# Power.net
KiCad netlist of a schematic drawn in Altium Designer
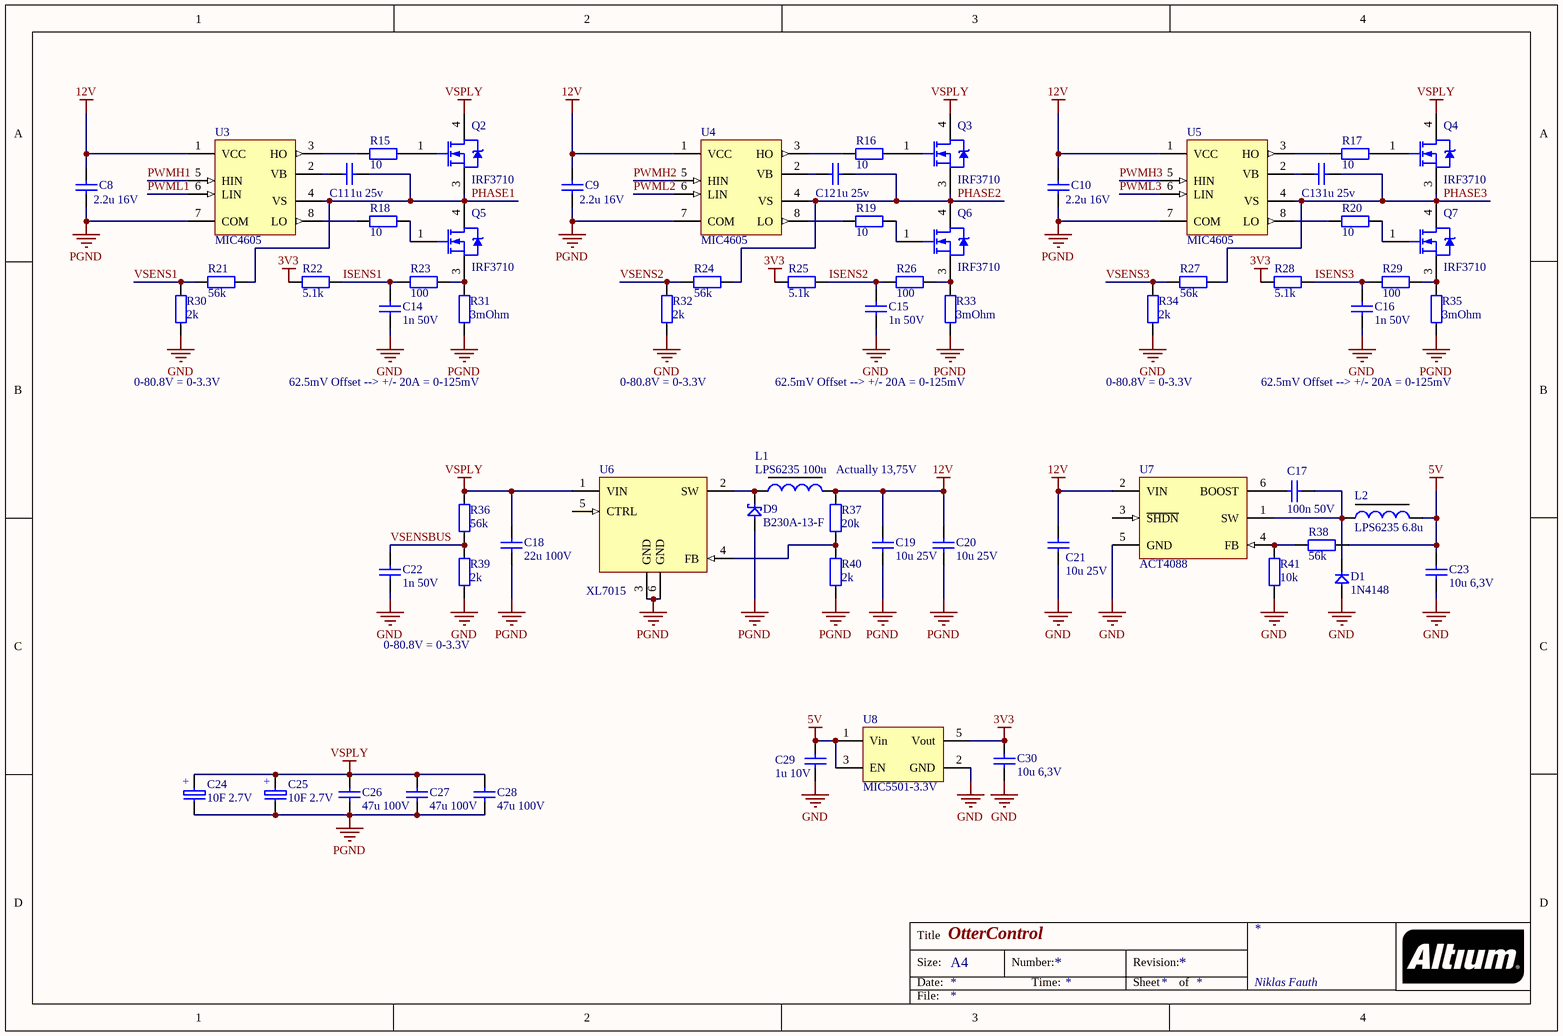
[diagram p0: Power.SchDoc]

(export (version "E")
  (design (tool "Eeschema 10.0.6"))
  (components
    (comp (ref "C8")
      (value "2.2u 16V")
      (footprint "C-0603-M")
      (description "Capacitor 2.2uF 16V")
      (libsource (lib "Passives") (part "C-0603-2u2-16V"))
    )
    (comp (ref "C9")
      (value "2.2u 16V")
      (footprint "C-0603-M")
      (description "Capacitor 2.2uF 16V")
      (libsource (lib "Passives") (part "C-0603-2u2-16V"))
    )
    (comp (ref "C10")
      (value "2.2u 16V")
      (footprint "C-0603-M")
      (description "Capacitor 2.2uF 16V")
      (libsource (lib "Passives") (part "C-0603-2u2-16V"))
    )
    (comp (ref "C11")
      (value "1u 25v")
      (footprint "C-0603-H")
      (description "Capacitor 1uF 25V")
      (libsource (lib "Passives") (part "C-0603-1u-25V"))
    )
    (comp (ref "C12")
      (value "1u 25v")
      (footprint "C-0603-H")
      (description "Capacitor 1uF 25V")
      (libsource (lib "Passives") (part "C-0603-1u-25V"))
    )
    (comp (ref "C13")
      (value "1u 25v")
      (footprint "C-0603-H")
      (description "Capacitor 1uF 25V")
      (libsource (lib "Passives") (part "C-0603-1u-25V"))
    )
    (comp (ref "C14")
      (value "1n 50V")
      (footprint "C-0603-H")
      (description "Capacitor 1nF 50V")
      (libsource (lib "Passives") (part "C-0603-1n-50V"))
    )
    (comp (ref "C15")
      (value "1n 50V")
      (footprint "C-0603-H")
      (description "Capacitor 1nF 50V")
      (libsource (lib "Passives") (part "C-0603-1n-50V"))
    )
    (comp (ref "C16")
      (value "1n 50V")
      (footprint "C-0603-H")
      (description "Capacitor 1nF 50V")
      (libsource (lib "Passives") (part "C-0603-1n-50V"))
    )
    (comp (ref "C17")
      (value "100n 50V")
      (footprint "C-0603-H")
      (description "Capacitor 100n 50V")
      (libsource (lib "Passives") (part "C-0603-100n-50V"))
    )
    (comp (ref "C18")
      (value "22u 100V")
      (footprint "C-2220")
      (description "Capacitor 47uF 100V")
      (libsource (lib "Passives") (part "C-2220-15u-100V"))
    )
    (comp (ref "C19")
      (value "10u 25V")
      (footprint "C-1206-H")
      (description "Capacitor 10uF 25V")
      (libsource (lib "Passives") (part "C-1206-10u-25V"))
    )
    (comp (ref "C20")
      (value "10u 25V")
      (footprint "C-1206-H")
      (description "Capacitor 10uF 25V")
      (libsource (lib "Passives") (part "C-1206-10u-25V"))
    )
    (comp (ref "C21")
      (value "10u 25V")
      (footprint "C-1206-H")
      (description "Capacitor 10uF 25V")
      (libsource (lib "Passives") (part "C-1206-10u-25V"))
    )
    (comp (ref "C22")
      (value "1n 50V")
      (footprint "C-0603-H")
      (description "Capacitor 1nF 50V")
      (libsource (lib "Passives") (part "C-0603-1n-50V"))
    )
    (comp (ref "C23")
      (value "10u 6,3V")
      (footprint "C-0603-H")
      (description "Capacitor 10uF 6,3V")
      (libsource (lib "Passives") (part "C-0603-10u-6,3V"))
    )
    (comp (ref "C24")
      (value "10F 2.7V")
      (footprint "12.5x31.5-angle")
      (description "supercap 10F 2.7V")
      (libsource (lib "Passives") (part "SC-10F-2.7V"))
    )
    (comp (ref "C25")
      (value "10F 2.7V")
      (footprint "12.5x31.5-angle")
      (description "supercap 10F 2.7V")
      (libsource (lib "Passives") (part "SC-10F-2.7V"))
    )
    (comp (ref "C26")
      (value "47u 100V")
      (footprint "C-2220")
      (description "Capacitor 47uF 100V")
      (libsource (lib "Passives") (part "C-2220-15u-100V"))
    )
    (comp (ref "C27")
      (value "47u 100V")
      (footprint "C-2220")
      (description "Capacitor 47uF 100V")
      (libsource (lib "Passives") (part "C-2220-15u-100V"))
    )
    (comp (ref "C28")
      (value "47u 100V")
      (footprint "C-2220")
      (description "Capacitor 47uF 100V")
      (libsource (lib "Passives") (part "C-2220-15u-100V"))
    )
    (comp (ref "C29")
      (value "1u 10V")
      (footprint "C-0603-M")
      (description "Capacitor 1uF 10V")
      (libsource (lib "Passives") (part "C-0603-1u-10V"))
    )
    (comp (ref "C30")
      (value "10u 6,3V")
      (footprint "C-0603-H")
      (description "Capacitor 10uF 6,3V")
      (libsource (lib "Passives") (part "C-0603-10u-6,3V"))
    )
    (comp (ref "D1")
      (value "1N4148")
      (footprint "SOD323F")
      (description "Diode 1N4148")
      (libsource (lib "advanced") (part "1N4148"))
    )
    (comp (ref "D9")
      (value "B230A-13-F")
      (footprint "DIODE-SMA")
      (libsource (lib "advanced") (part "D-B230A-13-F"))
    )
    (comp (ref "L1")
      (value "LPS6235 100u")
      (footprint "LPS6235")
      (libsource (lib "Passives") (part "L-LPS6235-68u"))
    )
    (comp (ref "L2")
      (value "LPS6235 6.8u")
      (footprint "LPS6235")
      (libsource (lib "Passives") (part "L-LPS6235-6u8"))
    )
    (comp (ref "Q2")
      (value "IRF3710")
      (footprint "ONSC-D2PAK-3-418B-04_V")
      (description "Power MOSFET, 37 A, 150 V, N-Channel Enhancement-Mode, 3-Pin D2PAK, Pb-Free, Tube")
      (fields (field (name "MANUFACTURER") "On Semiconductor") (field (name "PARTNUMBER") "NTB35N15G"))
      (libsource (lib "Altium Content Vault") (part "ONSC-NMOS-G1S3D4-3_C"))
    )
    (comp (ref "Q3")
      (value "IRF3710")
      (footprint "ONSC-D2PAK-3-418B-04_V")
      (description "Power MOSFET, 37 A, 150 V, N-Channel Enhancement-Mode, 3-Pin D2PAK, Pb-Free, Tube")
      (fields (field (name "MANUFACTURER") "On Semiconductor") (field (name "PARTNUMBER") "NTB35N15G"))
      (libsource (lib "Altium Content Vault") (part "ONSC-NMOS-G1S3D4-3_C"))
    )
    (comp (ref "Q4")
      (value "IRF3710")
      (footprint "ONSC-D2PAK-3-418B-04_V")
      (description "Power MOSFET, 37 A, 150 V, N-Channel Enhancement-Mode, 3-Pin D2PAK, Pb-Free, Tube")
      (fields (field (name "MANUFACTURER") "On Semiconductor") (field (name "PARTNUMBER") "NTB35N15G"))
      (libsource (lib "Altium Content Vault") (part "ONSC-NMOS-G1S3D4-3_C"))
    )
    (comp (ref "Q5")
      (value "IRF3710")
      (footprint "ONSC-D2PAK-3-418B-04_V")
      (description "Power MOSFET, 37 A, 150 V, N-Channel Enhancement-Mode, 3-Pin D2PAK, Pb-Free, Tube")
      (fields (field (name "MANUFACTURER") "On Semiconductor") (field (name "PARTNUMBER") "NTB35N15G"))
      (libsource (lib "Altium Content Vault") (part "ONSC-NMOS-G1S3D4-3_C"))
    )
    (comp (ref "Q6")
      (value "IRF3710")
      (footprint "ONSC-D2PAK-3-418B-04_V")
      (description "Power MOSFET, 37 A, 150 V, N-Channel Enhancement-Mode, 3-Pin D2PAK, Pb-Free, Tube")
      (fields (field (name "MANUFACTURER") "On Semiconductor") (field (name "PARTNUMBER") "NTB35N15G"))
      (libsource (lib "Altium Content Vault") (part "ONSC-NMOS-G1S3D4-3_C"))
    )
    (comp (ref "Q7")
      (value "IRF3710")
      (footprint "ONSC-D2PAK-3-418B-04_V")
      (description "Power MOSFET, 37 A, 150 V, N-Channel Enhancement-Mode, 3-Pin D2PAK, Pb-Free, Tube")
      (fields (field (name "MANUFACTURER") "On Semiconductor") (field (name "PARTNUMBER") "NTB35N15G"))
      (libsource (lib "Altium Content Vault") (part "ONSC-NMOS-G1S3D4-3_C"))
    )
    (comp (ref "R15")
      (value "10")
      (footprint "R-0603-H")
      (description "Resistor 10")
      (libsource (lib "Passives") (part "R-0603-10"))
    )
    (comp (ref "R16")
      (value "10")
      (footprint "R-0603-H")
      (description "Resistor 10")
      (libsource (lib "Passives") (part "R-0603-10"))
    )
    (comp (ref "R17")
      (value "10")
      (footprint "R-0603-H")
      (description "Resistor 10")
      (libsource (lib "Passives") (part "R-0603-10"))
    )
    (comp (ref "R18")
      (value "10")
      (footprint "R-0603-H")
      (description "Resistor 10")
      (libsource (lib "Passives") (part "R-0603-10"))
    )
    (comp (ref "R19")
      (value "10")
      (footprint "R-0603-H")
      (description "Resistor 10")
      (libsource (lib "Passives") (part "R-0603-10"))
    )
    (comp (ref "R20")
      (value "10")
      (footprint "R-0603-H")
      (description "Resistor 10")
      (libsource (lib "Passives") (part "R-0603-10"))
    )
    (comp (ref "R21")
      (value "56k")
      (footprint "R-0603-H")
      (description "Resistor 4k7")
      (libsource (lib "Passives") (part "R-0603-47k"))
    )
    (comp (ref "R22")
      (value "5.1k")
      (footprint "R-0603-H")
      (description "Resistor 5.1k")
      (libsource (lib "Passives") (part "R-0603-5k1"))
    )
    (comp (ref "R23")
      (value "100")
      (footprint "R-0603-H")
      (description "Resistor 100")
      (libsource (lib "Passives") (part "R-0603-100"))
    )
    (comp (ref "R24")
      (value "56k")
      (footprint "R-0603-H")
      (description "Resistor 4k7")
      (libsource (lib "Passives") (part "R-0603-47k"))
    )
    (comp (ref "R25")
      (value "5.1k")
      (footprint "R-0603-H")
      (description "Resistor 5.1k")
      (libsource (lib "Passives") (part "R-0603-5k1"))
    )
    (comp (ref "R26")
      (value "100")
      (footprint "R-0603-H")
      (description "Resistor 100")
      (libsource (lib "Passives") (part "R-0603-100"))
    )
    (comp (ref "R27")
      (value "56k")
      (footprint "R-0603-H")
      (description "Resistor 4k7")
      (libsource (lib "Passives") (part "R-0603-47k"))
    )
    (comp (ref "R28")
      (value "5.1k")
      (footprint "R-0603-H")
      (description "Resistor 5.1k")
      (libsource (lib "Passives") (part "R-0603-5k1"))
    )
    (comp (ref "R29")
      (value "100")
      (footprint "R-0603-H")
      (description "Resistor 100")
      (libsource (lib "Passives") (part "R-0603-100"))
    )
    (comp (ref "R30")
      (value "2k")
      (footprint "R-0603-M")
      (description "Resistor 2k")
      (libsource (lib "Passives") (part "R-0603-2k"))
    )
    (comp (ref "R31")
      (value "3mOhm")
      (footprint "R-1206-M")
      (description "Resistor 0")
      (libsource (lib "Passives") (part "R-1206-0"))
    )
    (comp (ref "R32")
      (value "2k")
      (footprint "R-0603-M")
      (description "Resistor 2k")
      (libsource (lib "Passives") (part "R-0603-2k"))
    )
    (comp (ref "R33")
      (value "3mOhm")
      (footprint "R-1206-M")
      (description "Resistor 0")
      (libsource (lib "Passives") (part "R-1206-0"))
    )
    (comp (ref "R34")
      (value "2k")
      (footprint "R-0603-M")
      (description "Resistor 2k")
      (libsource (lib "Passives") (part "R-0603-2k"))
    )
    (comp (ref "R35")
      (value "3mOhm")
      (footprint "R-1206-M")
      (description "Resistor 0")
      (libsource (lib "Passives") (part "R-1206-0"))
    )
    (comp (ref "R36")
      (value "56k")
      (footprint "R-0603-H")
      (description "Resistor 4k7")
      (libsource (lib "") (part "R-0603-47k_1"))
    )
    (comp (ref "R37")
      (value "20k")
      (footprint "R-0603-H")
      (description "Resistor 20k")
      (libsource (lib "Passives") (part "R-0603-20k"))
    )
    (comp (ref "R38")
      (value "56k")
      (footprint "R-0603-H")
      (description "Resistor 4k7")
      (libsource (lib "Passives") (part "R-0603-47k"))
    )
    (comp (ref "R39")
      (value "2k")
      (footprint "R-0603-M")
      (description "Resistor 2k")
      (libsource (lib "Passives") (part "R-0603-2k"))
    )
    (comp (ref "R40")
      (value "2k")
      (footprint "R-0603-H")
      (description "Resistor 2k")
      (libsource (lib "Passives") (part "R-0603-2k"))
    )
    (comp (ref "R41")
      (value "10k")
      (footprint "R-0603-H")
      (description "Resistor 15k")
      (libsource (lib "Passives") (part "R-0603-15k"))
    )
    (comp (ref "U3") (value "MIC4605") (footprint "SOIC-8") (libsource (lib "advanced") (part "MIC4605")))
    (comp (ref "U4") (value "MIC4605") (footprint "SOIC-8") (libsource (lib "advanced") (part "MIC4605")))
    (comp (ref "U5") (value "MIC4605") (footprint "SOIC-8") (libsource (lib "advanced") (part "MIC4605")))
    (comp (ref "U6")
      (value "XL7015")
      (footprint "DPAK127P970X238-6L")
      (description "High Voltage StepDown")
      (libsource (lib "advanced") (part "XL7015"))
    )
    (comp (ref "U7") (value "ACT4088") (footprint "SOT23-6") (libsource (lib "advanced") (part "ACT4088")))
    (comp (ref "U8")
      (value "MIC5501-3.3V")
      (footprint "SOT23-5")
      (libsource (lib "advanced") (part "MIC5501-3.3V"))
    )
  )
  (nets
    (net (code "1") (name "/ISENS1") (class "Default")
      (node (ref "C14") (pin "2") (pinfunction "2_2") (pintype "passive"))
      (node (ref "R22") (pin "2") (pinfunction "2_2") (pintype "passive"))
      (node (ref "R23") (pin "1") (pinfunction "1_1") (pintype "passive"))
    )
    (net (code "2") (name "/ISENS2") (class "Default")
      (node (ref "C15") (pin "2") (pinfunction "2_2") (pintype "passive"))
      (node (ref "R25") (pin "2") (pinfunction "2_2") (pintype "passive"))
      (node (ref "R26") (pin "1") (pinfunction "1_1") (pintype "passive"))
    )
    (net (code "3") (name "/ISENS3") (class "Default")
      (node (ref "C16") (pin "2") (pinfunction "2_2") (pintype "passive"))
      (node (ref "R28") (pin "2") (pinfunction "2_2") (pintype "passive"))
      (node (ref "R29") (pin "1") (pinfunction "1_1") (pintype "passive"))
    )
    (net (code "4") (name "/PHASE1") (class "Default")
      (node (ref "C11") (pin "2") (pinfunction "2_2") (pintype "passive"))
      (node (ref "Q2") (pin "3") (pinfunction "S_3") (pintype "passive"))
      (node (ref "Q5") (pin "4") (pinfunction "D_4") (pintype "passive"))
      (node (ref "R21") (pin "2") (pinfunction "2_2") (pintype "passive"))
      (node (ref "U3") (pin "4") (pinfunction "VS_4") (pintype "power_in"))
    )
    (net (code "5") (name "/PHASE2") (class "Default")
      (node (ref "C12") (pin "2") (pinfunction "2_2") (pintype "passive"))
      (node (ref "Q3") (pin "3") (pinfunction "S_3") (pintype "passive"))
      (node (ref "Q6") (pin "4") (pinfunction "D_4") (pintype "passive"))
      (node (ref "R24") (pin "2") (pinfunction "2_2") (pintype "passive"))
      (node (ref "U4") (pin "4") (pinfunction "VS_4") (pintype "power_in"))
    )
    (net (code "6") (name "/PHASE3") (class "Default")
      (node (ref "C13") (pin "2") (pinfunction "2_2") (pintype "passive"))
      (node (ref "Q4") (pin "3") (pinfunction "S_3") (pintype "passive"))
      (node (ref "Q7") (pin "4") (pinfunction "D_4") (pintype "passive"))
      (node (ref "R27") (pin "2") (pinfunction "2_2") (pintype "passive"))
      (node (ref "U5") (pin "4") (pinfunction "VS_4") (pintype "power_in"))
    )
    (net (code "7") (name "/PWMH1") (class "Default")
      (node (ref "U3") (pin "5") (pinfunction "HIN_5") (pintype "input"))
    )
    (net (code "8") (name "/PWMH2") (class "Default")
      (node (ref "U4") (pin "5") (pinfunction "HIN_5") (pintype "input"))
    )
    (net (code "9") (name "/PWMH3") (class "Default")
      (node (ref "U5") (pin "5") (pinfunction "HIN_5") (pintype "input"))
    )
    (net (code "10") (name "/PWML1") (class "Default")
      (node (ref "U3") (pin "6") (pinfunction "LIN_6") (pintype "input"))
    )
    (net (code "11") (name "/PWML2") (class "Default")
      (node (ref "U4") (pin "6") (pinfunction "LIN_6") (pintype "input"))
    )
    (net (code "12") (name "/PWML3") (class "Default")
      (node (ref "U5") (pin "6") (pinfunction "LIN_6") (pintype "input"))
    )
    (net (code "13") (name "/VSENS1") (class "Default")
      (node (ref "R21") (pin "1") (pinfunction "1_1") (pintype "passive"))
      (node (ref "R30") (pin "2") (pinfunction "2_2") (pintype "passive"))
    )
    (net (code "14") (name "/VSENS2") (class "Default")
      (node (ref "R24") (pin "1") (pinfunction "1_1") (pintype "passive"))
      (node (ref "R32") (pin "2") (pinfunction "2_2") (pintype "passive"))
    )
    (net (code "15") (name "/VSENS3") (class "Default")
      (node (ref "R27") (pin "1") (pinfunction "1_1") (pintype "passive"))
      (node (ref "R34") (pin "2") (pinfunction "2_2") (pintype "passive"))
    )
    (net (code "16") (name "/VSENSBUS") (class "Default")
      (node (ref "C22") (pin "2") (pinfunction "2_2") (pintype "passive"))
      (node (ref "R36") (pin "1") (pinfunction "1_1") (pintype "passive"))
      (node (ref "R39") (pin "2") (pinfunction "2_2") (pintype "passive"))
    )
    (net (code "17") (name "3V3") (class "Default")
      (node (ref "C30") (pin "2") (pinfunction "2_2") (pintype "passive"))
      (node (ref "R22") (pin "1") (pinfunction "1_1") (pintype "passive"))
      (node (ref "R25") (pin "1") (pinfunction "1_1") (pintype "passive"))
      (node (ref "R28") (pin "1") (pinfunction "1_1") (pintype "passive"))
      (node (ref "U8") (pin "5") (pinfunction "Vout_5") (pintype "passive"))
    )
    (net (code "18") (name "5V") (class "Default")
      (node (ref "C23") (pin "2") (pinfunction "2_2") (pintype "passive"))
      (node (ref "C29") (pin "2") (pinfunction "2_2") (pintype "passive"))
      (node (ref "L2") (pin "2") (pinfunction "2_2") (pintype "passive"))
      (node (ref "R38") (pin "2") (pinfunction "2_2") (pintype "passive"))
      (node (ref "U8") (pin "1") (pinfunction "Vin_1") (pintype "passive"))
      (node (ref "U8") (pin "3") (pinfunction "EN_3") (pintype "passive"))
    )
    (net (code "19") (name "12V") (class "Default")
      (node (ref "C10") (pin "2") (pinfunction "2_2") (pintype "passive"))
      (node (ref "C19") (pin "2") (pinfunction "2_2") (pintype "passive"))
      (node (ref "C20") (pin "2") (pinfunction "2_2") (pintype "passive"))
      (node (ref "C21") (pin "2") (pinfunction "2_2") (pintype "passive"))
      (node (ref "C8") (pin "2") (pinfunction "2_2") (pintype "passive"))
      (node (ref "C9") (pin "2") (pinfunction "2_2") (pintype "passive"))
      (node (ref "L1") (pin "2") (pinfunction "2_2") (pintype "passive"))
      (node (ref "R37") (pin "2") (pinfunction "2_2") (pintype "passive"))
      (node (ref "U3") (pin "1") (pinfunction "VCC_1") (pintype "power_in"))
      (node (ref "U4") (pin "1") (pinfunction "VCC_1") (pintype "power_in"))
      (node (ref "U5") (pin "1") (pinfunction "VCC_1") (pintype "power_in"))
      (node (ref "U7") (pin "2") (pinfunction "VIN_2") (pintype "power_in"))
    )
    (net (code "20") (name "GND") (class "Default")
      (node (ref "C14") (pin "1") (pinfunction "1_1") (pintype "passive"))
      (node (ref "C15") (pin "1") (pinfunction "1_1") (pintype "passive"))
      (node (ref "C16") (pin "1") (pinfunction "1_1") (pintype "passive"))
      (node (ref "C21") (pin "1") (pinfunction "1_1") (pintype "passive"))
      (node (ref "C22") (pin "1") (pinfunction "1_1") (pintype "passive"))
      (node (ref "C23") (pin "1") (pinfunction "1_1") (pintype "passive"))
      (node (ref "C29") (pin "1") (pinfunction "1_1") (pintype "passive"))
      (node (ref "C30") (pin "1") (pinfunction "1_1") (pintype "passive"))
      (node (ref "D1") (pin "1") (pinfunction "an_1") (pintype "passive"))
      (node (ref "R30") (pin "1") (pinfunction "1_1") (pintype "passive"))
      (node (ref "R32") (pin "1") (pinfunction "1_1") (pintype "passive"))
      (node (ref "R34") (pin "1") (pinfunction "1_1") (pintype "passive"))
      (node (ref "R39") (pin "1") (pinfunction "1_1") (pintype "passive"))
      (node (ref "R41") (pin "1") (pinfunction "1_1") (pintype "passive"))
      (node (ref "U7") (pin "5") (pinfunction "GND_5") (pintype "power_in"))
      (node (ref "U8") (pin "2") (pinfunction "GND_2") (pintype "passive"))
    )
    (net (code "21") (name "Net-(D1-kt)") (class "Default")
      (node (ref "C17") (pin "2") (pinfunction "2_2") (pintype "passive"))
      (node (ref "D1") (pin "2") (pinfunction "kt_2") (pintype "passive"))
      (node (ref "L2") (pin "1") (pinfunction "1_1") (pintype "passive"))
      (node (ref "U7") (pin "1") (pinfunction "SW_1") (pintype "power_in"))
    )
    (net (code "22") (name "Net-(D9-kt)") (class "Default")
      (node (ref "D9") (pin "2") (pinfunction "kt_2") (pintype "passive"))
      (node (ref "L1") (pin "1") (pinfunction "1_1") (pintype "passive"))
      (node (ref "U6") (pin "2") (pinfunction "SW_2") (pintype "power_in"))
    )
    (net (code "23") (name "Net-(Q2-G)") (class "Default")
      (node (ref "Q2") (pin "1") (pinfunction "G_1") (pintype "passive"))
      (node (ref "R15") (pin "2") (pinfunction "2_2") (pintype "passive"))
    )
    (net (code "24") (name "Net-(Q3-G)") (class "Default")
      (node (ref "Q3") (pin "1") (pinfunction "G_1") (pintype "passive"))
      (node (ref "R16") (pin "2") (pinfunction "2_2") (pintype "passive"))
    )
    (net (code "25") (name "Net-(Q4-G)") (class "Default")
      (node (ref "Q4") (pin "1") (pinfunction "G_1") (pintype "passive"))
      (node (ref "R17") (pin "2") (pinfunction "2_2") (pintype "passive"))
    )
    (net (code "26") (name "Net-(Q5-G)") (class "Default")
      (node (ref "Q5") (pin "1") (pinfunction "G_1") (pintype "passive"))
      (node (ref "R18") (pin "2") (pinfunction "2_2") (pintype "passive"))
    )
    (net (code "27") (name "Net-(Q5-S)") (class "Default")
      (node (ref "Q5") (pin "3") (pinfunction "S_3") (pintype "passive"))
      (node (ref "R23") (pin "2") (pinfunction "2_2") (pintype "passive"))
      (node (ref "R31") (pin "2") (pinfunction "2_2") (pintype "passive"))
    )
    (net (code "28") (name "Net-(Q6-G)") (class "Default")
      (node (ref "Q6") (pin "1") (pinfunction "G_1") (pintype "passive"))
      (node (ref "R19") (pin "2") (pinfunction "2_2") (pintype "passive"))
    )
    (net (code "29") (name "Net-(Q6-S)") (class "Default")
      (node (ref "Q6") (pin "3") (pinfunction "S_3") (pintype "passive"))
      (node (ref "R26") (pin "2") (pinfunction "2_2") (pintype "passive"))
      (node (ref "R33") (pin "2") (pinfunction "2_2") (pintype "passive"))
    )
    (net (code "30") (name "Net-(Q7-G)") (class "Default")
      (node (ref "Q7") (pin "1") (pinfunction "G_1") (pintype "passive"))
      (node (ref "R20") (pin "2") (pinfunction "2_2") (pintype "passive"))
    )
    (net (code "31") (name "Net-(Q7-S)") (class "Default")
      (node (ref "Q7") (pin "3") (pinfunction "S_3") (pintype "passive"))
      (node (ref "R29") (pin "2") (pinfunction "2_2") (pintype "passive"))
      (node (ref "R35") (pin "2") (pinfunction "2_2") (pintype "passive"))
    )
    (net (code "32") (name "Net-(U3-HO)") (class "Default")
      (node (ref "R15") (pin "1") (pinfunction "1_1") (pintype "passive"))
      (node (ref "U3") (pin "3") (pinfunction "HO_3") (pintype "output"))
    )
    (net (code "33") (name "Net-(U3-LO)") (class "Default")
      (node (ref "R18") (pin "1") (pinfunction "1_1") (pintype "passive"))
      (node (ref "U3") (pin "8") (pinfunction "LO_8") (pintype "output"))
    )
    (net (code "34") (name "Net-(U3-VB)") (class "Default")
      (node (ref "C11") (pin "1") (pinfunction "1_1") (pintype "passive"))
      (node (ref "U3") (pin "2") (pinfunction "VB_2") (pintype "power_in"))
    )
    (net (code "35") (name "Net-(U4-HO)") (class "Default")
      (node (ref "R16") (pin "1") (pinfunction "1_1") (pintype "passive"))
      (node (ref "U4") (pin "3") (pinfunction "HO_3") (pintype "output"))
    )
    (net (code "36") (name "Net-(U4-LO)") (class "Default")
      (node (ref "R19") (pin "1") (pinfunction "1_1") (pintype "passive"))
      (node (ref "U4") (pin "8") (pinfunction "LO_8") (pintype "output"))
    )
    (net (code "37") (name "Net-(U4-VB)") (class "Default")
      (node (ref "C12") (pin "1") (pinfunction "1_1") (pintype "passive"))
      (node (ref "U4") (pin "2") (pinfunction "VB_2") (pintype "power_in"))
    )
    (net (code "38") (name "Net-(U5-HO)") (class "Default")
      (node (ref "R17") (pin "1") (pinfunction "1_1") (pintype "passive"))
      (node (ref "U5") (pin "3") (pinfunction "HO_3") (pintype "output"))
    )
    (net (code "39") (name "Net-(U5-LO)") (class "Default")
      (node (ref "R20") (pin "1") (pinfunction "1_1") (pintype "passive"))
      (node (ref "U5") (pin "8") (pinfunction "LO_8") (pintype "output"))
    )
    (net (code "40") (name "Net-(U5-VB)") (class "Default")
      (node (ref "C13") (pin "1") (pinfunction "1_1") (pintype "passive"))
      (node (ref "U5") (pin "2") (pinfunction "VB_2") (pintype "power_in"))
    )
    (net (code "41") (name "Net-(U6-FB)") (class "Default")
      (node (ref "R37") (pin "1") (pinfunction "1_1") (pintype "passive"))
      (node (ref "R40") (pin "2") (pinfunction "2_2") (pintype "passive"))
      (node (ref "U6") (pin "4") (pinfunction "FB_4") (pintype "input"))
    )
    (net (code "42") (name "Net-(U7-BOOST)") (class "Default")
      (node (ref "C17") (pin "1") (pinfunction "1_1") (pintype "passive"))
      (node (ref "U7") (pin "6") (pinfunction "BOOST_6") (pintype "passive"))
    )
    (net (code "43") (name "Net-(U7-FB)") (class "Default")
      (node (ref "R38") (pin "1") (pinfunction "1_1") (pintype "passive"))
      (node (ref "R41") (pin "2") (pinfunction "2_2") (pintype "passive"))
      (node (ref "U7") (pin "4") (pinfunction "FB_4") (pintype "input"))
    )
    (net (code "44") (name "PGND") (class "Default")
      (node (ref "C10") (pin "1") (pinfunction "1_1") (pintype "passive"))
      (node (ref "C18") (pin "1") (pinfunction "1_1") (pintype "passive"))
      (node (ref "C19") (pin "1") (pinfunction "1_1") (pintype "passive"))
      (node (ref "C20") (pin "1") (pinfunction "1_1") (pintype "passive"))
      (node (ref "C24") (pin "2") (pinfunction "2_2") (pintype "passive"))
      (node (ref "C25") (pin "2") (pinfunction "2_2") (pintype "passive"))
      (node (ref "C26") (pin "1") (pinfunction "1_1") (pintype "passive"))
      (node (ref "C27") (pin "1") (pinfunction "1_1") (pintype "passive"))
      (node (ref "C28") (pin "1") (pinfunction "1_1") (pintype "passive"))
      (node (ref "C8") (pin "1") (pinfunction "1_1") (pintype "passive"))
      (node (ref "C9") (pin "1") (pinfunction "1_1") (pintype "passive"))
      (node (ref "D9") (pin "1") (pinfunction "an_1") (pintype "passive"))
      (node (ref "R31") (pin "1") (pinfunction "1_1") (pintype "passive"))
      (node (ref "R33") (pin "1") (pinfunction "1_1") (pintype "passive"))
      (node (ref "R35") (pin "1") (pinfunction "1_1") (pintype "passive"))
      (node (ref "R40") (pin "1") (pinfunction "1_1") (pintype "passive"))
      (node (ref "U3") (pin "7") (pinfunction "COM_7") (pintype "passive"))
      (node (ref "U4") (pin "7") (pinfunction "COM_7") (pintype "passive"))
      (node (ref "U5") (pin "7") (pinfunction "COM_7") (pintype "passive"))
      (node (ref "U6") (pin "3") (pinfunction "GND_3") (pintype "power_in"))
      (node (ref "U6") (pin "6") (pinfunction "GND_6") (pintype "power_in"))
    )
    (net (code "45") (name "VSPLY") (class "Default")
      (node (ref "C18") (pin "2") (pinfunction "2_2") (pintype "passive"))
      (node (ref "C24") (pin "1") (pinfunction "1_1") (pintype "passive"))
      (node (ref "C25") (pin "1") (pinfunction "1_1") (pintype "passive"))
      (node (ref "C26") (pin "2") (pinfunction "2_2") (pintype "passive"))
      (node (ref "C27") (pin "2") (pinfunction "2_2") (pintype "passive"))
      (node (ref "C28") (pin "2") (pinfunction "2_2") (pintype "passive"))
      (node (ref "Q2") (pin "4") (pinfunction "D_4") (pintype "passive"))
      (node (ref "Q3") (pin "4") (pinfunction "D_4") (pintype "passive"))
      (node (ref "Q4") (pin "4") (pinfunction "D_4") (pintype "passive"))
      (node (ref "R36") (pin "2") (pinfunction "2_2") (pintype "passive"))
      (node (ref "U6") (pin "1") (pinfunction "VIN_1") (pintype "power_in"))
    )
    (net (code "46") (name "unconnected-(U6-CTRL-Pad5)") (class "Default")
      (node (ref "U6") (pin "5") (pinfunction "CTRL_5") (pintype "input"))
    )
    (net (code "47") (name "unconnected-(U7-~{SHDN}-Pad3)") (class "Default")
      (node (ref "U7") (pin "3") (pinfunction "~{SHDN}_3") (pintype "input"))
    )
  )
)
